# Level_shifter.net
KiCad netlist of a schematic drawn in Altium Designer
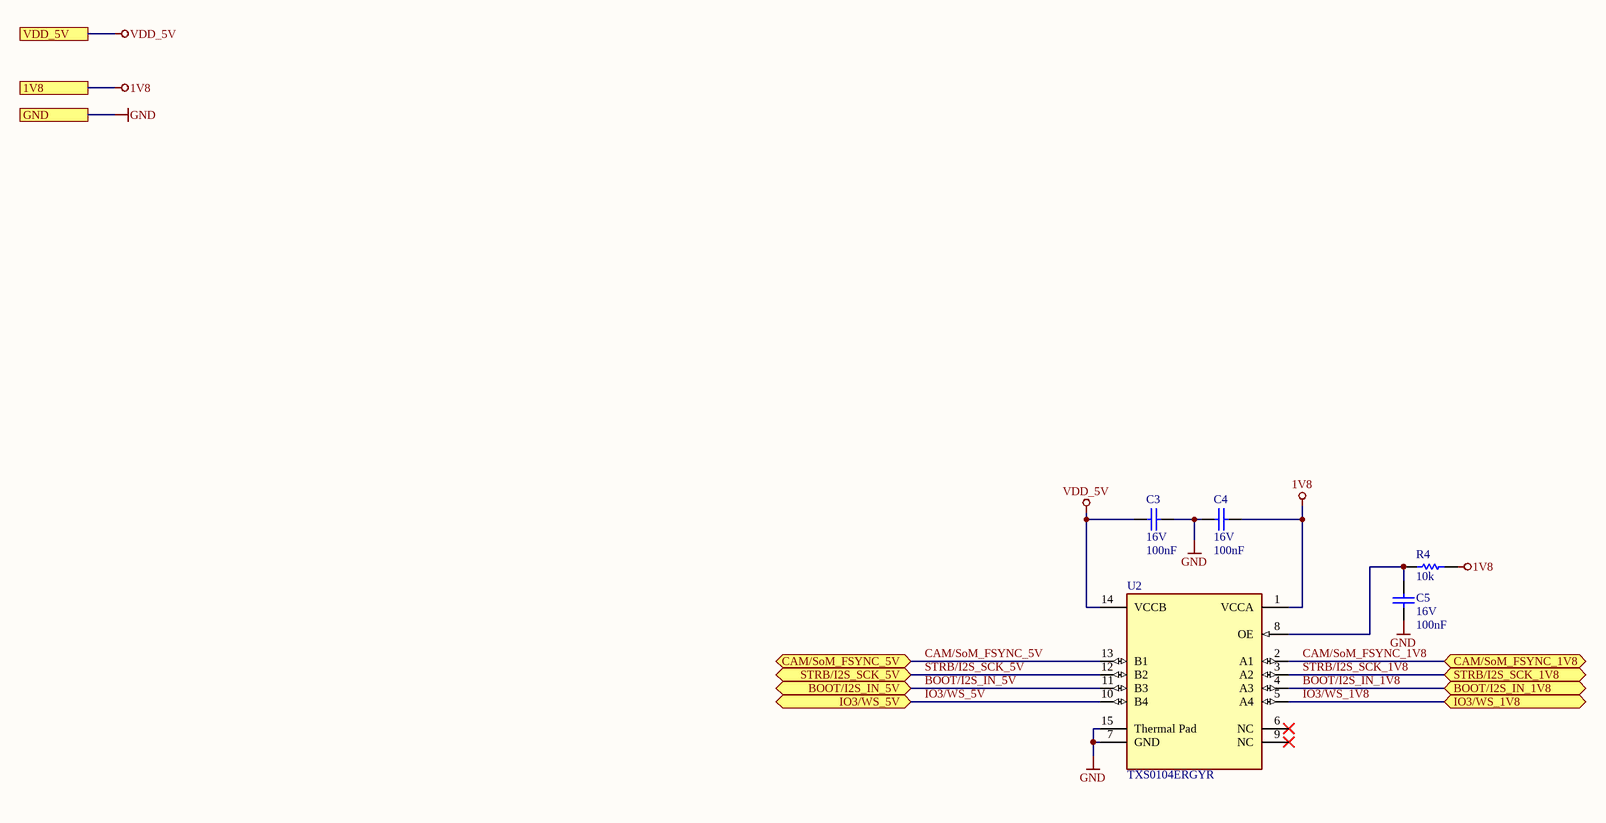
[diagram p0: Level_shifter.SchDoc]

(export (version "E")
  (design (tool "Eeschema 10.0.6"))
  (components
    (comp (ref "C3")
      (value "100nF")
      (footprint "CAPC0402(1005)60_N")
      (description "CAP CER 0.1UF 16V X7R 0402 10%")
      (fields
        (field (name "VOLTAGE RATING") "16V")
        (field (name "TOLERANCE") "10%")
        (field (name "Comment") "CL05B104KO5NFNC")
      )
      (libsource (lib "Luxonis LLC") (part "GRM188R61C475KAAJD"))
    )
    (comp (ref "C4")
      (value "100nF")
      (footprint "CAPC0402(1005)60_N")
      (description "CAP CER 0.1UF 16V X7R 0402 10%")
      (fields
        (field (name "VOLTAGE RATING") "16V")
        (field (name "TOLERANCE") "10%")
        (field (name "Comment") "CL05B104KO5NFNC")
      )
      (libsource (lib "Luxonis LLC") (part "GRM188R61C475KAAJD"))
    )
    (comp (ref "C5")
      (value "100nF")
      (footprint "CAPC0402(1005)60_N")
      (description "CAP CER 0.1UF 16V X7R 0402 10%")
      (fields
        (field (name "VOLTAGE RATING") "16V")
        (field (name "TOLERANCE") "10%")
        (field (name "Comment") "CL05B104KO5NFNC")
      )
      (libsource (lib "Luxonis LLC") (part "GRM188R61C475KAAJD"))
    )
    (comp (ref "R4")
      (value "10k")
      (footprint "RESC0402(1005)_N")
      (description "RES SMD 10K OHM 1% 1/16W 0402")
      (fields (field (name "TOLERANCE") "1%") (field (name "Comment") "RC0402FR-1310KL"))
      (libsource (lib "Luxonis LLC") (part "RC0402FR-0722RL_1"))
    )
    (comp (ref "U2")
      (value "TXS0104ERGYR")
      (footprint "FP-RGY0014A-MFG")
      (description "Interface Circuit, PQCC14")
      (libsource (lib "Luxonis LLC") (part "3faf5fc5dddc1ed78575e524fca393d"))
    )
  )
  (nets
    (net (code "1") (name "/BOOT{slash}I2S_IN_1V8") (class "Default")
      (node (ref "U2") (pin "4") (pinfunction "A3_4") (pintype "bidirectional"))
    )
    (net (code "2") (name "/BOOT{slash}I2S_IN_5V") (class "Default")
      (node (ref "U2") (pin "11") (pinfunction "B3_11") (pintype "bidirectional"))
    )
    (net (code "3") (name "/CAM{slash}SoM_FSYNC_1V8") (class "Default")
      (node (ref "U2") (pin "2") (pinfunction "A1_2") (pintype "bidirectional"))
    )
    (net (code "4") (name "/CAM{slash}SoM_FSYNC_5V") (class "Default")
      (node (ref "U2") (pin "13") (pinfunction "B1_13") (pintype "bidirectional"))
    )
    (net (code "5") (name "/IO3{slash}WS_1V8") (class "Default")
      (node (ref "U2") (pin "5") (pinfunction "A4_5") (pintype "bidirectional"))
    )
    (net (code "6") (name "/IO3{slash}WS_5V") (class "Default")
      (node (ref "U2") (pin "10") (pinfunction "B4_10") (pintype "bidirectional"))
    )
    (net (code "7") (name "/STRB{slash}I2S_SCK_1V8") (class "Default")
      (node (ref "U2") (pin "3") (pinfunction "A2_3") (pintype "bidirectional"))
    )
    (net (code "8") (name "/STRB{slash}I2S_SCK_5V") (class "Default")
      (node (ref "U2") (pin "12") (pinfunction "B2_12") (pintype "bidirectional"))
    )
    (net (code "9") (name "1V8") (class "Default")
      (node (ref "C4") (pin "2") (pinfunction "2_2") (pintype "passive"))
      (node (ref "R4") (pin "2") (pinfunction "2_2") (pintype "passive"))
      (node (ref "U2") (pin "1") (pinfunction "VCCA_1") (pintype "power_in"))
    )
    (net (code "10") (name "GND") (class "Default")
      (node (ref "C3") (pin "2") (pinfunction "2_2") (pintype "passive"))
      (node (ref "C4") (pin "1") (pinfunction "1_1") (pintype "passive"))
      (node (ref "C5") (pin "1") (pinfunction "1_1") (pintype "passive"))
      (node (ref "U2") (pin "15") (pinfunction "Thermal_Pad_15") (pintype "power_in"))
      (node (ref "U2") (pin "7") (pinfunction "GND_7") (pintype "power_in"))
    )
    (net (code "11") (name "Net-(U2-OE)") (class "Default")
      (node (ref "C5") (pin "2") (pinfunction "2_2") (pintype "passive"))
      (node (ref "R4") (pin "1") (pinfunction "1_1") (pintype "passive"))
      (node (ref "U2") (pin "8") (pinfunction "OE_8") (pintype "input"))
    )
    (net (code "12") (name "VDD_5V") (class "Default")
      (node (ref "C3") (pin "1") (pinfunction "1_1") (pintype "passive"))
      (node (ref "U2") (pin "14") (pinfunction "VCCB_14") (pintype "power_in"))
    )
    (net (code "13") (name "unconnected-(U2-NC-Pad6)") (class "Default")
      (node (ref "U2") (pin "6") (pinfunction "NC_6") (pintype "passive+no_connect"))
    )
    (net (code "14") (name "unconnected-(U2-NC-Pad9)") (class "Default")
      (node (ref "U2") (pin "9") (pinfunction "NC_9") (pintype "passive+no_connect"))
    )
  )
)
